# LED_Driver.net
KiCad netlist of a schematic drawn in Altium Designer
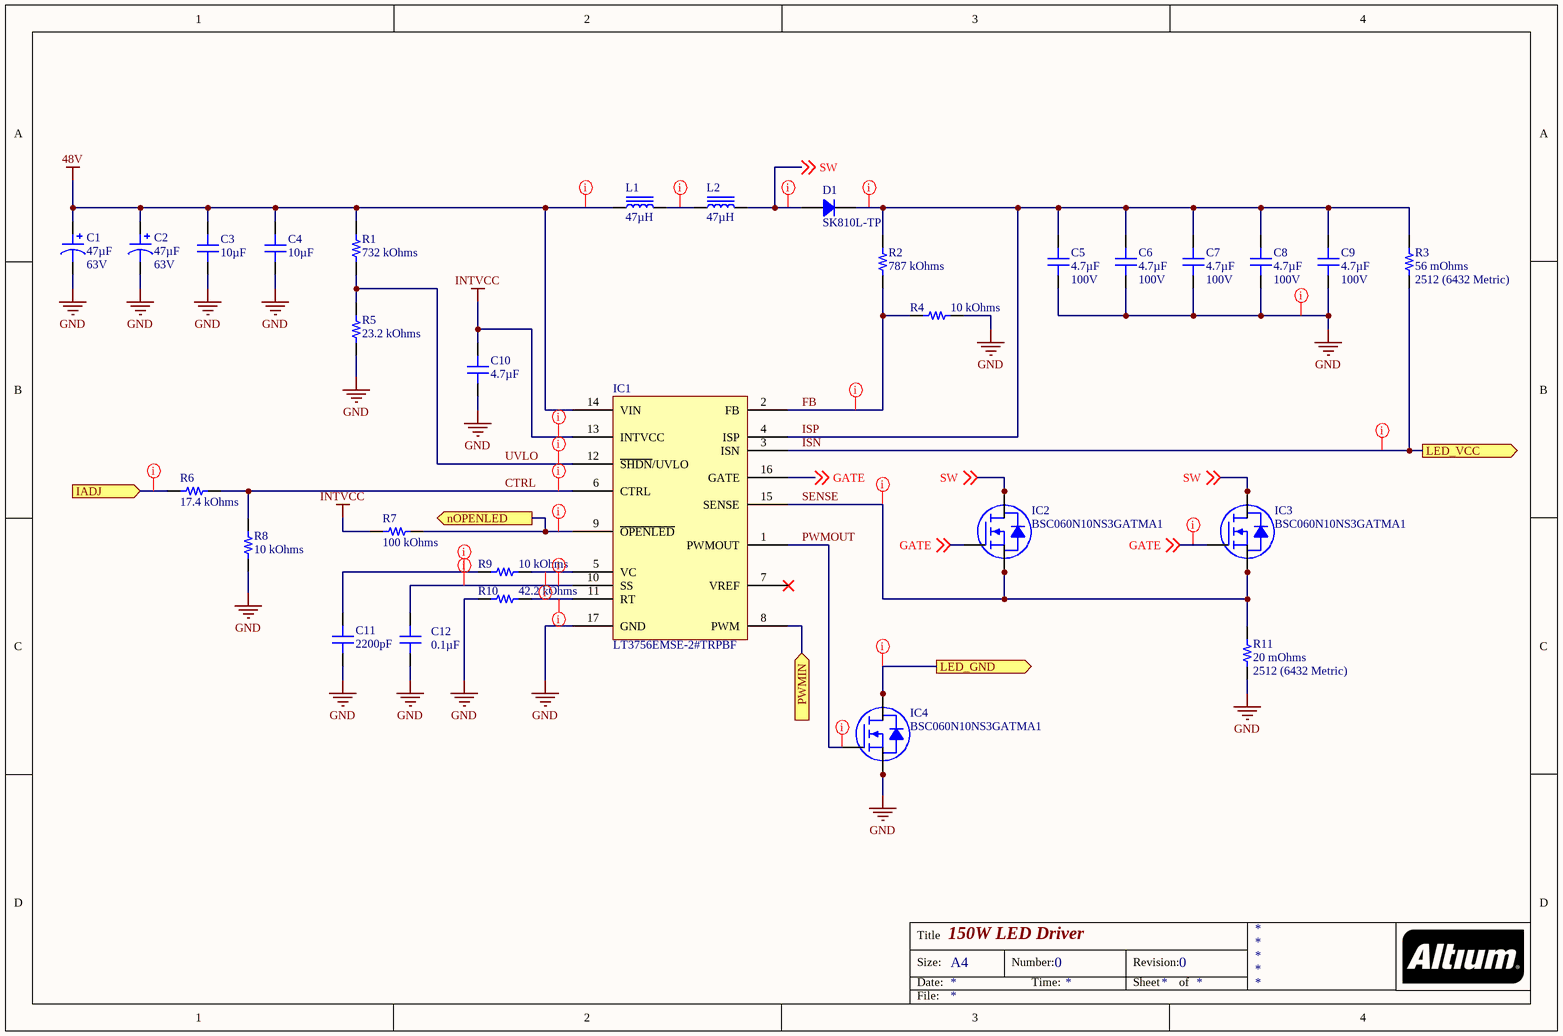
[diagram p0: LED Driver.SchDoc]

(export (version "E")
  (design (tool "Eeschema 10.0.6"))
  (components
    (comp (ref "C1")
      (value "47µF")
      (footprint "CAP ALSMD 8.3MM H10.5MM")
      (description "CAP ALUM 47UF 20% 63V SMD")
      (fields
        (field (name "PART NUMBER") "63SEV47M8X10.5")
        (field (name "MANUFACTURER") "Rubycon")
        (field (name "VOLTAGE - RATED") "63V")
      )
      (libsource (lib "Celestial Altium Library - altium_library") (part "Polarised Capacitor"))
    )
    (comp (ref "C2")
      (value "47µF")
      (footprint "CAP ALSMD 8.3MM H10.5MM")
      (description "CAP ALUM 47UF 20% 63V SMD")
      (fields
        (field (name "PART NUMBER") "63SEV47M8X10.5")
        (field (name "MANUFACTURER") "Rubycon")
        (field (name "VOLTAGE - RATED") "63V")
      )
      (libsource (lib "Celestial Altium Library - altium_library") (part "Polarised Capacitor"))
    )
    (comp (ref "C3")
      (value "10µF")
      (footprint "CAP 1210_3225 - 2.8MM")
      (description "CAP CER 10UF 63V X7R 1210")
      (fields
        (field (name "PART NUMBER") "CL32B106KMVNNWE")
        (field (name "MANUFACTURER") "Samsung Electro-Mechanics")
      )
      (libsource (lib "Celestial Altium Library - altium_library") (part "Capacitor"))
    )
    (comp (ref "C4")
      (value "10µF")
      (footprint "CAP 1210_3225 - 2.8MM")
      (description "CAP CER 10UF 63V X7R 1210")
      (fields
        (field (name "PART NUMBER") "CL32B106KMVNNWE")
        (field (name "MANUFACTURER") "Samsung Electro-Mechanics")
      )
      (libsource (lib "Celestial Altium Library - altium_library") (part "Capacitor"))
    )
    (comp (ref "C5")
      (value "4.7µF")
      (footprint "CAP 1210_3225 - 2.8MM")
      (description "CAP CER 4.7UF 100V X5R 1210")
      (fields
        (field (name "PART NUMBER") "HMK325BJ475KM-PE")
        (field (name "MANUFACTURER") "Taiyo Yuden")
        (field (name "VOLTAGE - RATED") "100V")
      )
      (libsource (lib "Celestial Altium Library - altium_library") (part "Capacitor"))
    )
    (comp (ref "C6")
      (value "4.7µF")
      (footprint "CAP 1210_3225 - 2.8MM")
      (description "CAP CER 4.7UF 100V X5R 1210")
      (fields
        (field (name "PART NUMBER") "HMK325BJ475KM-PE")
        (field (name "MANUFACTURER") "Taiyo Yuden")
        (field (name "VOLTAGE - RATED") "100V")
      )
      (libsource (lib "Celestial Altium Library - altium_library") (part "Capacitor"))
    )
    (comp (ref "C7")
      (value "4.7µF")
      (footprint "CAP 1210_3225 - 2.8MM")
      (description "CAP CER 4.7UF 100V X5R 1210")
      (fields
        (field (name "PART NUMBER") "HMK325BJ475KM-PE")
        (field (name "MANUFACTURER") "Taiyo Yuden")
        (field (name "VOLTAGE - RATED") "100V")
      )
      (libsource (lib "Celestial Altium Library - altium_library") (part "Capacitor"))
    )
    (comp (ref "C8")
      (value "4.7µF")
      (footprint "CAP 1210_3225 - 2.8MM")
      (description "CAP CER 4.7UF 100V X5R 1210")
      (fields
        (field (name "PART NUMBER") "HMK325BJ475KM-PE")
        (field (name "MANUFACTURER") "Taiyo Yuden")
        (field (name "VOLTAGE - RATED") "100V")
      )
      (libsource (lib "Celestial Altium Library - altium_library") (part "Capacitor"))
    )
    (comp (ref "C9")
      (value "4.7µF")
      (footprint "CAP 1210_3225 - 2.8MM")
      (description "CAP CER 4.7UF 100V X5R 1210")
      (fields
        (field (name "PART NUMBER") "HMK325BJ475KM-PE")
        (field (name "MANUFACTURER") "Taiyo Yuden")
        (field (name "VOLTAGE - RATED") "100V")
      )
      (libsource (lib "Celestial Altium Library - altium_library") (part "Capacitor"))
    )
    (comp (ref "C10")
      (value "4.7µF")
      (footprint "CAP 0402_1005")
      (description "CAP CER 4.7UF 10V X5R 0402")
      (fields
        (field (name "PART NUMBER") "GRM155R61A475MEAAD")
        (field (name "MANUFACTURER") "Murata Electronics")
      )
      (libsource (lib "Celestial Altium Library - altium_library") (part "Capacitor"))
    )
    (comp (ref "C11")
      (value "2200pF")
      (footprint "CAP 0402_1005")
      (description "CAP CER 2200PF 50V X7R 0402")
      (fields
        (field (name "PART NUMBER") "GRM155R71H222JA01J")
        (field (name "MANUFACTURER") "Murata Electronics")
      )
      (libsource (lib "Celestial Altium Library - altium_library") (part "Capacitor"))
    )
    (comp (ref "C12")
      (value "0.1µF")
      (footprint "CAP 0402_1005")
      (description "CAP CER 0.1UF 16V X5R 0402")
      (fields (field (name "PART NUMBER") "EMK105BJ104MV-F") (field (name "MANUFACTURER") "Taiyo Yuden"))
      (libsource (lib "Celestial Altium Library - altium_library") (part "Capacitor"))
    )
    (comp (ref "D1")
      (value "SK810L-TP")
      (footprint "DO214AB SMC")
      (description "DIODE SCHOTTKY 100V 8A DO214AB")
      (fields (field (name "MANUFACTURER") "Micro Commercial Co"))
      (libsource (lib "Celestial Altium Library - altium_library") (part "Diode"))
    )
    (comp (ref "IC1")
      (value "LT3756EMSE-2#TRPBF")
      (footprint "LTC MSOP-16 MSE16")
      (description "IC LED DRIVER CTRLR DIM 16MSOP")
      (fields (field (name "MANUFACTURER") "Linear Technology/Analog Devices"))
      (libsource (lib "Celestial Altium Library - altium_library") (part "LINEAR TECH LT3756EMSE-2"))
    )
    (comp (ref "IC2")
      (value "BSC060N10NS3GATMA1")
      (footprint "INFINEON PG-TDSON-8")
      (description "MOSFET N-CH 100V 90A TDSON-8")
      (fields (field (name "MANUFACTURER") "Infineon Technologies"))
      (libsource (lib "Celestial Altium Library - altium_library") (part "INFINEON BSC MOSFET N-CH"))
    )
    (comp (ref "IC3")
      (value "BSC060N10NS3GATMA1")
      (footprint "INFINEON PG-TDSON-8")
      (description "MOSFET N-CH 100V 90A TDSON-8")
      (fields (field (name "MANUFACTURER") "Infineon Technologies"))
      (libsource (lib "Celestial Altium Library - altium_library") (part "INFINEON BSC MOSFET N-CH"))
    )
    (comp (ref "IC4")
      (value "BSC060N10NS3GATMA1")
      (footprint "INFINEON PG-TDSON-8")
      (description "MOSFET N-CH 100V 90A TDSON-8")
      (fields (field (name "MANUFACTURER") "Infineon Technologies"))
      (libsource (lib "Celestial Altium Library - altium_library") (part "INFINEON BSC MOSFET N-CH"))
    )
    (comp (ref "L1")
      (value "47µH")
      (footprint "WURTH WE-HCF 14.5MM")
      (description "FIXED IND 47UH 12A 12.2 MOHM SMD")
      (fields (field (name "PART NUMBER") "7443634700") (field (name "MANUFACTURER") "Würth Elektronik"))
      (libsource (lib "Celestial Altium Library - altium_library") (part "Inductor"))
    )
    (comp (ref "L2")
      (value "47µH")
      (footprint "WURTH WE-HCF 14.5MM")
      (description "FIXED IND 47UH 12A 12.2 MOHM SMD")
      (fields (field (name "PART NUMBER") "7443634700") (field (name "MANUFACTURER") "Würth Elektronik"))
      (libsource (lib "Celestial Altium Library - altium_library") (part "Inductor"))
    )
    (comp (ref "R1")
      (value "732 kOhms")
      (footprint "RES 0402_1005")
      (description "RES SMD 732K OHM 1% 1/10W 0402")
      (fields
        (field (name "PART NUMBER") "ERJ-2RKF7323X")
        (field (name "MANUFACTURER") "Panasonic Electronic Components")
      )
      (libsource (lib "Celestial Altium Library - altium_library") (part "Resistor"))
    )
    (comp (ref "R2")
      (value "787 kOhms")
      (footprint "RES 0402_1005")
      (description "RES SMD 787K OHM 1% 1/10W 0402")
      (fields
        (field (name "PART NUMBER") "ERJ-2RKF7873X")
        (field (name "MANUFACTURER") "Panasonic Electronic Components")
      )
      (libsource (lib "Celestial Altium Library - altium_library") (part "Resistor"))
    )
    (comp (ref "R3")
      (value "56 mOhms")
      (footprint "STACKPOLE CSR2512")
      (description "RES 0.056 OHM 1% 1W 3264")
      (fields
        (field (name "PART NUMBER") "KRL3264-C-R056-F-T1")
        (field (name "MANUFACTURER") "Susumu")
        (field (name "PACKAGE / CASE") "2512 (6432 Metric)")
      )
      (libsource (lib "Celestial Altium Library - altium_library") (part "Resistor"))
    )
    (comp (ref "R4")
      (value "10 kOhms")
      (footprint "RES 0402_1005")
      (description "RES SMD 10K OHM 1% 1/10W 0402")
      (fields
        (field (name "PART NUMBER") "ERJ-2RKF1002X")
        (field (name "MANUFACTURER") "Panasonic Electronic Components")
      )
      (libsource (lib "Celestial Altium Library - altium_library") (part "Resistor"))
    )
    (comp (ref "R5")
      (value "23.2 kOhms")
      (footprint "RES 0402_1005")
      (description "RES SMD 23.2K OHM 1% 1/10W 0402")
      (fields
        (field (name "PART NUMBER") "ERJ-2RKF2322X")
        (field (name "MANUFACTURER") "Panasonic Electronic Components")
      )
      (libsource (lib "Celestial Altium Library - altium_library") (part "Resistor"))
    )
    (comp (ref "R6")
      (value "17.4 kOhms")
      (footprint "RES 0402_1005")
      (description "RES SMD 17.4K OHM 1% 1/10W 0402")
      (fields
        (field (name "PART NUMBER") "ERJ-2RKF1742X")
        (field (name "MANUFACTURER") "Panasonic Electronic Components")
      )
      (libsource (lib "Celestial Altium Library - altium_library") (part "Resistor"))
    )
    (comp (ref "R7")
      (value "100 kOhms")
      (footprint "RES 0402_1005")
      (description "RES SMD 100K OHM 5% 1/5W 0402")
      (fields
        (field (name "PART NUMBER") "ERJ-PA2J104X")
        (field (name "MANUFACTURER") "Panasonic Electronic Components")
      )
      (libsource (lib "Celestial Altium Library - altium_library") (part "Resistor"))
    )
    (comp (ref "R8")
      (value "10 kOhms")
      (footprint "RES 0402_1005")
      (description "RES SMD 10K OHM 1% 1/10W 0402")
      (fields
        (field (name "PART NUMBER") "ERJ-2RKF1002X")
        (field (name "MANUFACTURER") "Panasonic Electronic Components")
      )
      (libsource (lib "Celestial Altium Library - altium_library") (part "Resistor"))
    )
    (comp (ref "R9")
      (value "10 kOhms")
      (footprint "RES 0402_1005")
      (description "RES SMD 10K OHM 1% 1/10W 0402")
      (fields
        (field (name "PART NUMBER") "ERJ-2RKF1002X")
        (field (name "MANUFACTURER") "Panasonic Electronic Components")
      )
      (libsource (lib "Celestial Altium Library - altium_library") (part "Resistor"))
    )
    (comp (ref "R10")
      (value "42.2 kOhms")
      (footprint "RES 0402_1005")
      (description "RES SMD 42.2K OHM 1% 1/10W 0402")
      (fields
        (field (name "PART NUMBER") "ERJ-2RKF4222X")
        (field (name "MANUFACTURER") "Panasonic Electronic Components")
      )
      (libsource (lib "Celestial Altium Library - altium_library") (part "Resistor"))
    )
    (comp (ref "R11")
      (value "20 mOhms")
      (footprint "STACKPOLE CSR2512")
      (description "RES 0.02 OHM 1% 2W 2512")
      (fields
        (field (name "PART NUMBER") "CSRN2512FK20L0")
        (field (name "MANUFACTURER") "Stackpole Electronics Inc")
        (field (name "PACKAGE / CASE") "2512 (6432 Metric)")
      )
      (libsource (lib "Celestial Altium Library - altium_library") (part "Resistor"))
    )
  )
  (nets
    (net (code "1") (name "/CTRL") (class "Default")
      (node (ref "IC1") (pin "6") (pinfunction "CTRL_6") (pintype "passive"))
      (node (ref "R6") (pin "2") (pinfunction "2_2") (pintype "passive"))
      (node (ref "R8") (pin "2") (pinfunction "2_2") (pintype "passive"))
    )
    (net (code "2") (name "/FB") (class "Default")
      (node (ref "IC1") (pin "2") (pinfunction "FB_2") (pintype "passive"))
      (node (ref "R2") (pin "1") (pinfunction "1_1") (pintype "passive"))
      (node (ref "R4") (pin "2") (pinfunction "2_2") (pintype "passive"))
    )
    (net (code "3") (name "/IADJ") (class "Default")
      (node (ref "R6") (pin "1") (pinfunction "1_1") (pintype "passive"))
    )
    (net (code "4") (name "/ISN") (class "Default")
      (node (ref "IC1") (pin "3") (pinfunction "ISN_3") (pintype "passive"))
      (node (ref "R3") (pin "1") (pinfunction "1_1") (pintype "passive"))
    )
    (net (code "5") (name "/ISP") (class "Default")
      (node (ref "C5") (pin "2") (pinfunction "2_2") (pintype "passive"))
      (node (ref "C6") (pin "2") (pinfunction "2_2") (pintype "passive"))
      (node (ref "C7") (pin "2") (pinfunction "2_2") (pintype "passive"))
      (node (ref "C8") (pin "2") (pinfunction "2_2") (pintype "passive"))
      (node (ref "C9") (pin "2") (pinfunction "2_2") (pintype "passive"))
      (node (ref "D1") (pin "2") (pinfunction "2_2") (pintype "passive"))
      (node (ref "IC1") (pin "4") (pinfunction "ISP_4") (pintype "passive"))
      (node (ref "R2") (pin "2") (pinfunction "2_2") (pintype "passive"))
      (node (ref "R3") (pin "2") (pinfunction "2_2") (pintype "passive"))
    )
    (net (code "6") (name "/LED_GND") (class "Default")
      (node (ref "IC4") (pin "5") (pinfunction "D_5") (pintype "passive"))
      (node (ref "IC4") (pin "6") (pinfunction "D_6") (pintype "passive"))
      (node (ref "IC4") (pin "7") (pinfunction "D_7") (pintype "passive"))
      (node (ref "IC4") (pin "8") (pinfunction "D_8") (pintype "passive"))
    )
    (net (code "7") (name "/PWMIN") (class "Default")
      (node (ref "IC1") (pin "8") (pinfunction "PWM_8") (pintype "passive"))
    )
    (net (code "8") (name "/PWMOUT") (class "Default")
      (node (ref "IC1") (pin "1") (pinfunction "PWMOUT_1") (pintype "passive"))
      (node (ref "IC4") (pin "4") (pinfunction "G_4") (pintype "passive"))
    )
    (net (code "9") (name "/SENSE") (class "Default")
      (node (ref "IC1") (pin "15") (pinfunction "SENSE_15") (pintype "passive"))
      (node (ref "IC2") (pin "1") (pinfunction "S_1") (pintype "passive"))
      (node (ref "IC2") (pin "2") (pinfunction "S_2") (pintype "passive"))
      (node (ref "IC2") (pin "3") (pinfunction "S_3") (pintype "passive"))
      (node (ref "IC3") (pin "1") (pinfunction "S_1") (pintype "passive"))
      (node (ref "IC3") (pin "2") (pinfunction "S_2") (pintype "passive"))
      (node (ref "IC3") (pin "3") (pinfunction "S_3") (pintype "passive"))
      (node (ref "R11") (pin "2") (pinfunction "2_2") (pintype "passive"))
    )
    (net (code "10") (name "/UVLO") (class "Default")
      (node (ref "IC1") (pin "12") (pinfunction "~{SHDN}/UVLO_12") (pintype "passive"))
      (node (ref "R1") (pin "1") (pinfunction "1_1") (pintype "passive"))
      (node (ref "R5") (pin "2") (pinfunction "2_2") (pintype "passive"))
    )
    (net (code "11") (name "/nOPENLED") (class "Default")
      (node (ref "IC1") (pin "9") (pinfunction "~{OPENLED}_9") (pintype "passive"))
      (node (ref "R7") (pin "2") (pinfunction "2_2") (pintype "passive"))
    )
    (net (code "12") (name "48V") (class "Default")
      (node (ref "C1") (pin "1") (pinfunction "1_1") (pintype "passive"))
      (node (ref "C2") (pin "1") (pinfunction "1_1") (pintype "passive"))
      (node (ref "C3") (pin "2") (pinfunction "2_2") (pintype "passive"))
      (node (ref "C4") (pin "2") (pinfunction "2_2") (pintype "passive"))
      (node (ref "IC1") (pin "14") (pinfunction "VIN_14") (pintype "passive"))
      (node (ref "L1") (pin "1") (pinfunction "1_1") (pintype "passive"))
      (node (ref "R1") (pin "2") (pinfunction "2_2") (pintype "passive"))
    )
    (net (code "13") (name "GATE") (class "Default")
      (node (ref "IC1") (pin "16") (pinfunction "GATE_16") (pintype "passive"))
      (node (ref "IC2") (pin "4") (pinfunction "G_4") (pintype "passive"))
      (node (ref "IC3") (pin "4") (pinfunction "G_4") (pintype "passive"))
    )
    (net (code "14") (name "GND") (class "Default")
      (node (ref "C1") (pin "2") (pinfunction "2_2") (pintype "passive"))
      (node (ref "C10") (pin "1") (pinfunction "1_1") (pintype "passive"))
      (node (ref "C11") (pin "1") (pinfunction "1_1") (pintype "passive"))
      (node (ref "C12") (pin "1") (pinfunction "1_1") (pintype "passive"))
      (node (ref "C2") (pin "2") (pinfunction "2_2") (pintype "passive"))
      (node (ref "C3") (pin "1") (pinfunction "1_1") (pintype "passive"))
      (node (ref "C4") (pin "1") (pinfunction "1_1") (pintype "passive"))
      (node (ref "C5") (pin "1") (pinfunction "1_1") (pintype "passive"))
      (node (ref "C6") (pin "1") (pinfunction "1_1") (pintype "passive"))
      (node (ref "C7") (pin "1") (pinfunction "1_1") (pintype "passive"))
      (node (ref "C8") (pin "1") (pinfunction "1_1") (pintype "passive"))
      (node (ref "C9") (pin "1") (pinfunction "1_1") (pintype "passive"))
      (node (ref "IC1") (pin "17") (pinfunction "GND_17") (pintype "passive"))
      (node (ref "IC4") (pin "1") (pinfunction "S_1") (pintype "passive"))
      (node (ref "IC4") (pin "2") (pinfunction "S_2") (pintype "passive"))
      (node (ref "IC4") (pin "3") (pinfunction "S_3") (pintype "passive"))
      (node (ref "R10") (pin "1") (pinfunction "1_1") (pintype "passive"))
      (node (ref "R11") (pin "1") (pinfunction "1_1") (pintype "passive"))
      (node (ref "R4") (pin "1") (pinfunction "1_1") (pintype "passive"))
      (node (ref "R5") (pin "1") (pinfunction "1_1") (pintype "passive"))
      (node (ref "R8") (pin "1") (pinfunction "1_1") (pintype "passive"))
    )
    (net (code "15") (name "INTVCC") (class "Default")
      (node (ref "C10") (pin "2") (pinfunction "2_2") (pintype "passive"))
      (node (ref "IC1") (pin "13") (pinfunction "INTVCC_13") (pintype "passive"))
      (node (ref "R7") (pin "1") (pinfunction "1_1") (pintype "passive"))
    )
    (net (code "16") (name "Net-(C11-Pad2)") (class "Default")
      (node (ref "C11") (pin "2") (pinfunction "2_2") (pintype "passive"))
      (node (ref "R9") (pin "2") (pinfunction "2_2") (pintype "passive"))
    )
    (net (code "17") (name "Net-(IC1-RT)") (class "Default")
      (node (ref "IC1") (pin "11") (pinfunction "RT_11") (pintype "passive"))
      (node (ref "R10") (pin "2") (pinfunction "2_2") (pintype "passive"))
    )
    (net (code "18") (name "Net-(IC1-SS)") (class "Default")
      (node (ref "C12") (pin "2") (pinfunction "2_2") (pintype "passive"))
      (node (ref "IC1") (pin "10") (pinfunction "SS_10") (pintype "passive"))
    )
    (net (code "19") (name "Net-(IC1-VC)") (class "Default")
      (node (ref "IC1") (pin "5") (pinfunction "VC_5") (pintype "passive"))
      (node (ref "R9") (pin "1") (pinfunction "1_1") (pintype "passive"))
    )
    (net (code "20") (name "Net-(L1-Pad2)") (class "Default")
      (node (ref "L1") (pin "2") (pinfunction "2_2") (pintype "passive"))
      (node (ref "L2") (pin "1") (pinfunction "1_1") (pintype "passive"))
    )
    (net (code "21") (name "SW") (class "Default")
      (node (ref "D1") (pin "1") (pinfunction "1_1") (pintype "passive"))
      (node (ref "IC2") (pin "5") (pinfunction "D_5") (pintype "passive"))
      (node (ref "IC2") (pin "6") (pinfunction "D_6") (pintype "passive"))
      (node (ref "IC2") (pin "7") (pinfunction "D_7") (pintype "passive"))
      (node (ref "IC2") (pin "8") (pinfunction "D_8") (pintype "passive"))
      (node (ref "IC3") (pin "5") (pinfunction "D_5") (pintype "passive"))
      (node (ref "IC3") (pin "6") (pinfunction "D_6") (pintype "passive"))
      (node (ref "IC3") (pin "7") (pinfunction "D_7") (pintype "passive"))
      (node (ref "IC3") (pin "8") (pinfunction "D_8") (pintype "passive"))
      (node (ref "L2") (pin "2") (pinfunction "2_2") (pintype "passive"))
    )
    (net (code "22") (name "unconnected-(IC1-VREF-Pad7)") (class "Default")
      (node (ref "IC1") (pin "7") (pinfunction "VREF_7") (pintype "passive+no_connect"))
    )
  )
)
